# test_nguyenLy.net
KiCad netlist of a schematic drawn in Altium Designer
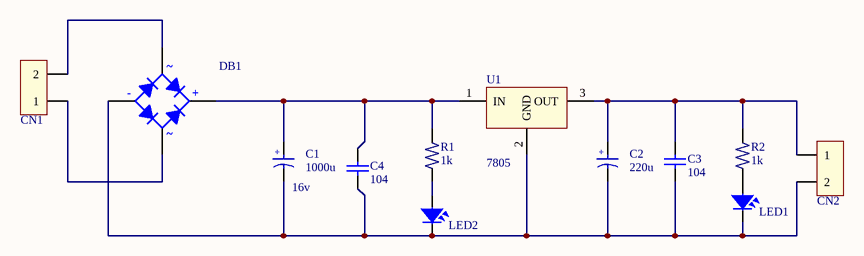
[diagram p0: test_nguyenLy.SchDoc]

(export (version "E")
  (design (tool "Eeschema 10.0.6"))
  (components
    (comp (ref "C1")
      (value "1000u")
      (footprint "Cap 10mm")
      (description "Cap Pol")
      (fields (field (name "VOLT") "16v"))
      (libsource (lib "sch") (part "Cap Pol"))
    )
    (comp (ref "C2")
      (value "220u")
      (footprint "Cap 10mm")
      (description "Cap Pol")
      (libsource (lib "sch") (part "Cap Pol"))
    )
    (comp (ref "C3")
      (value "104")
      (footprint "Cap Non Pol 3mm")
      (description "Cap Nol Pol")
      (libsource (lib "sch") (part "Cap Non Pol"))
    )
    (comp (ref "C4")
      (value "104")
      (footprint "Cap Non Pol 3mm")
      (description "Cap Nol Pol")
      (libsource (lib "sch") (part "Cap Non Pol"))
    )
    (comp (ref "CN1")
      (value "Con2/Header2")
      (footprint "Terminal Block2")
      (description "CON2")
      (libsource (lib "") (part "Con2/Header2_1"))
    )
    (comp (ref "CN2")
      (value "Con2/Header2")
      (footprint "Terminal Block2")
      (description "CON2")
      (libsource (lib "sch") (part "Con2/Header2"))
    )
    (comp (ref "DB1")
      (value "Diode bridge")
      (footprint "DIO-Bri 1A")
      (libsource (lib "sch") (part "Diode bridge"))
    )
    (comp (ref "LED1") (value "LED") (footprint "LED-5mm BLUE") (libsource (lib "sch") (part "LED")))
    (comp (ref "LED2") (value "LED") (footprint "LED-5mm BLUE") (libsource (lib "sch") (part "LED")))
    (comp (ref "R1")
      (value "1k")
      (footprint "RESISTOR 1/4W")
      (description "RESISTOR")
      (libsource (lib "sch") (part "RESISTOR"))
    )
    (comp (ref "R2")
      (value "1k")
      (footprint "RESISTOR 1/4W")
      (description "RESISTOR")
      (libsource (lib "sch") (part "RESISTOR"))
    )
    (comp (ref "U1")
      (value "7805")
      (footprint "QTO-220")
      (description "LM78xx, on ap +")
      (libsource (lib "sch") (part "78xx"))
    )
  )
  (nets
    (net (code "1") (name "Net-(CN1-Pad1)") (class "Default")
      (node (ref "CN1") (pin "1") (pinfunction "1_1") (pintype "passive"))
      (node (ref "DB1") (pin "3") (pinfunction "C_3") (pintype "passive"))
    )
    (net (code "2") (name "Net-(CN1-Pad2)") (class "Default")
      (node (ref "CN1") (pin "2") (pinfunction "2_2") (pintype "passive"))
      (node (ref "DB1") (pin "2") (pinfunction "C_2") (pintype "passive"))
    )
    (net (code "3") (name "Net-(DB1-A)") (class "Default")
      (node (ref "C1") (pin "2") (pinfunction "2_2") (pintype "passive"))
      (node (ref "C2") (pin "2") (pinfunction "2_2") (pintype "passive"))
      (node (ref "C3") (pin "1") (pinfunction "1_1") (pintype "passive"))
      (node (ref "C4") (pin "1") (pinfunction "1_1") (pintype "passive"))
      (node (ref "CN2") (pin "2") (pinfunction "2_2") (pintype "passive"))
      (node (ref "DB1") (pin "4") (pinfunction "A_4") (pintype "passive"))
      (node (ref "LED1") (pin "2") (pinfunction "2_2") (pintype "passive"))
      (node (ref "LED2") (pin "2") (pinfunction "2_2") (pintype "passive"))
      (node (ref "U1") (pin "2") (pinfunction "GND_2") (pintype "passive"))
    )
    (net (code "4") (name "Net-(DB1-K)") (class "Default")
      (node (ref "C1") (pin "1") (pinfunction "1_1") (pintype "passive"))
      (node (ref "C4") (pin "2") (pinfunction "2_2") (pintype "passive"))
      (node (ref "DB1") (pin "1") (pinfunction "K_1") (pintype "passive"))
      (node (ref "R1") (pin "2") (pinfunction "2_2") (pintype "passive"))
      (node (ref "U1") (pin "1") (pinfunction "IN_1") (pintype "passive"))
    )
    (net (code "5") (name "Net-(LED1-Pad1)") (class "Default")
      (node (ref "LED1") (pin "1") (pinfunction "1_1") (pintype "passive"))
      (node (ref "R2") (pin "1") (pinfunction "1_1") (pintype "passive"))
    )
    (net (code "6") (name "Net-(LED2-Pad1)") (class "Default")
      (node (ref "LED2") (pin "1") (pinfunction "1_1") (pintype "passive"))
      (node (ref "R1") (pin "1") (pinfunction "1_1") (pintype "passive"))
    )
    (net (code "7") (name "Net-(U1-OUT)") (class "Default")
      (node (ref "C2") (pin "1") (pinfunction "1_1") (pintype "passive"))
      (node (ref "C3") (pin "2") (pinfunction "2_2") (pintype "passive"))
      (node (ref "CN2") (pin "1") (pinfunction "1_1") (pintype "passive"))
      (node (ref "R2") (pin "2") (pinfunction "2_2") (pintype "passive"))
      (node (ref "U1") (pin "3") (pinfunction "OUT_3") (pintype "passive"))
    )
  )
)
